# ERN_MainPower_2.net
KiCad netlist of a schematic drawn in Altium Designer
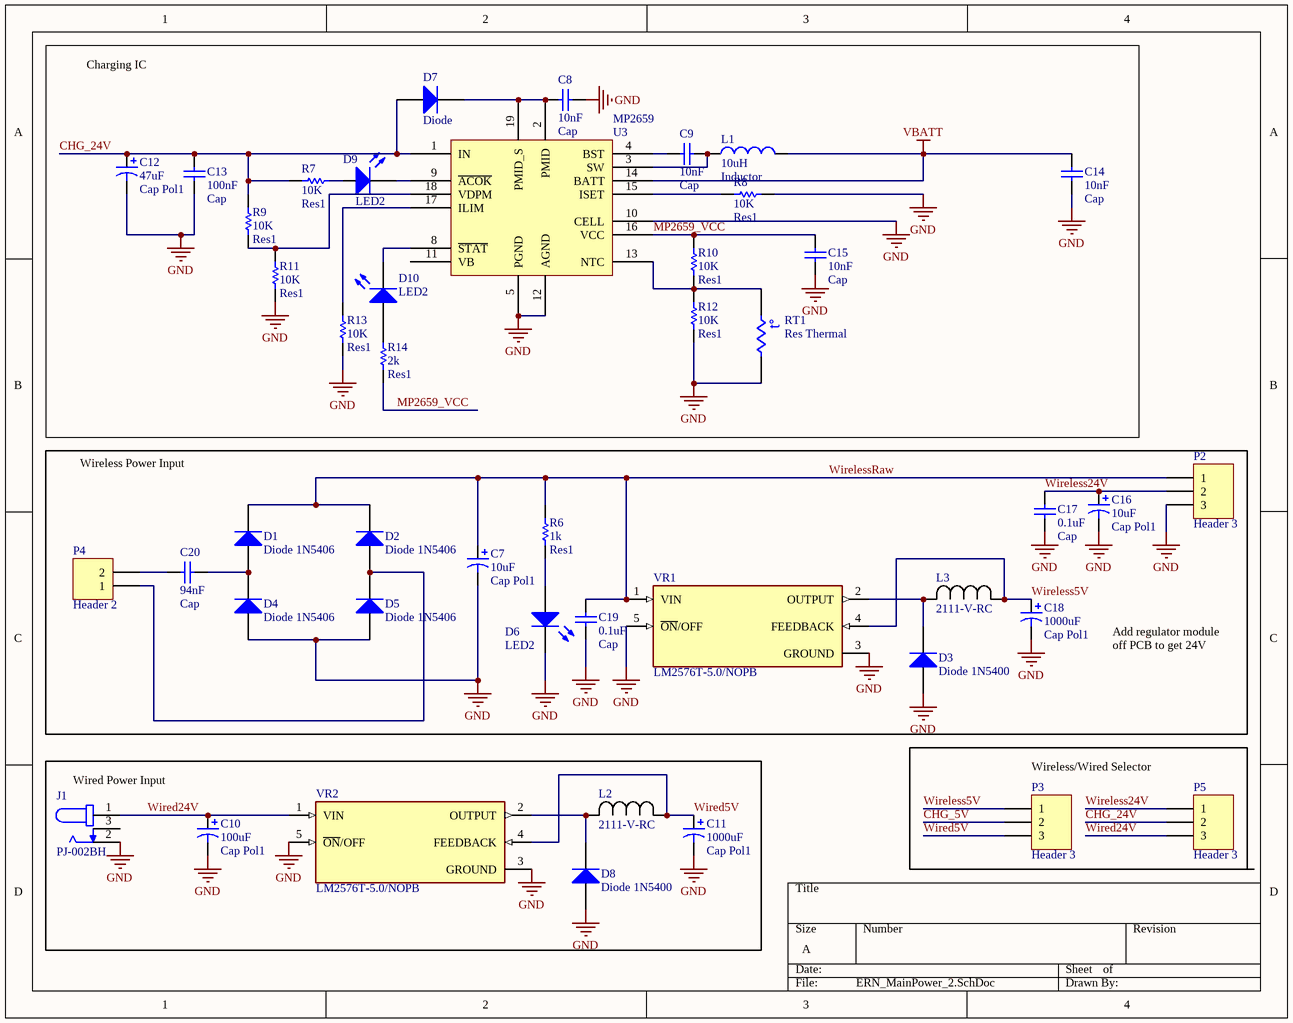
[diagram p0: ERN_MainPower_2.SchDoc]

(export (version "E")
  (design (tool "Eeschema 10.0.6"))
  (components
    (comp (ref "C7")
      (value "Cap Pol1")
      (footprint "RB7.6-15")
      (description "Polarized Capacitor (Radial)")
      (fields (field (name "ALTIUM_VALUE") "10uF") (field (name "PUBLISHER") "Altium Limited"))
      (libsource (lib "Miscellaneous Devices") (part "Cap Pol1"))
    )
    (comp (ref "C8")
      (value "Cap")
      (footprint "C0805")
      (description "Capacitor")
      (fields (field (name "ALTIUM_VALUE") "10nF") (field (name "PUBLISHER") "Altium Limited"))
      (libsource (lib "Miscellaneous Devices") (part "Cap"))
    )
    (comp (ref "C9")
      (value "Cap")
      (footprint "C0805")
      (description "Capacitor")
      (fields (field (name "ALTIUM_VALUE") "10nF") (field (name "PUBLISHER") "Altium Limited"))
      (libsource (lib "Miscellaneous Devices") (part "Cap"))
    )
    (comp (ref "C10")
      (value "Cap Pol1")
      (footprint "RB7.6-15")
      (description "Polarized Capacitor (Radial)")
      (fields (field (name "ALTIUM_VALUE") "100uF") (field (name "PUBLISHER") "Altium Limited"))
      (libsource (lib "Miscellaneous Devices") (part "Cap Pol1"))
    )
    (comp (ref "C11")
      (value "Cap Pol1")
      (footprint "RB7.6-15")
      (description "Polarized Capacitor (Radial)")
      (fields (field (name "ALTIUM_VALUE") "1000uF") (field (name "PUBLISHER") "Altium Limited"))
      (libsource (lib "Miscellaneous Devices") (part "Cap Pol1"))
    )
    (comp (ref "C12")
      (value "Cap Pol1")
      (footprint "RB7.6-15")
      (description "Polarized Capacitor (Radial)")
      (fields (field (name "ALTIUM_VALUE") "47uF") (field (name "PUBLISHER") "Altium Limited"))
      (libsource (lib "Miscellaneous Devices") (part "Cap Pol1"))
    )
    (comp (ref "C13")
      (value "Cap")
      (footprint "RAD-0.3")
      (description "Capacitor")
      (fields (field (name "ALTIUM_VALUE") "100nF") (field (name "PUBLISHER") "Altium Limited"))
      (libsource (lib "Miscellaneous Devices") (part "Cap"))
    )
    (comp (ref "C14")
      (value "Cap")
      (footprint "C0805")
      (description "Capacitor")
      (fields (field (name "ALTIUM_VALUE") "10nF") (field (name "PUBLISHER") "Altium Limited"))
      (libsource (lib "Miscellaneous Devices") (part "Cap"))
    )
    (comp (ref "C15")
      (value "Cap")
      (footprint "C0805")
      (description "Capacitor")
      (fields (field (name "ALTIUM_VALUE") "10nF") (field (name "PUBLISHER") "Altium Limited"))
      (libsource (lib "Miscellaneous Devices") (part "Cap"))
    )
    (comp (ref "C16")
      (value "Cap Pol1")
      (footprint "RB7.6-15")
      (description "Polarized Capacitor (Radial)")
      (fields (field (name "ALTIUM_VALUE") "10uF") (field (name "PUBLISHER") "Altium Limited"))
      (libsource (lib "Miscellaneous Devices") (part "Cap Pol1"))
    )
    (comp (ref "C17")
      (value "Cap")
      (footprint "RAD-0.3")
      (description "Capacitor")
      (fields (field (name "ALTIUM_VALUE") "0.1uF") (field (name "PUBLISHER") "Altium Limited"))
      (libsource (lib "Miscellaneous Devices") (part "Cap"))
    )
    (comp (ref "C18")
      (value "Cap Pol1")
      (footprint "RB7.6-15")
      (description "Polarized Capacitor (Radial)")
      (fields (field (name "ALTIUM_VALUE") "1000uF") (field (name "PUBLISHER") "Altium Limited"))
      (libsource (lib "Miscellaneous Devices") (part "Cap Pol1"))
    )
    (comp (ref "C19")
      (value "Cap")
      (footprint "RAD-0.3")
      (description "Capacitor")
      (fields (field (name "ALTIUM_VALUE") "0.1uF") (field (name "PUBLISHER") "Altium Limited"))
      (libsource (lib "Miscellaneous Devices") (part "Cap"))
    )
    (comp (ref "C20")
      (value "Cap")
      (footprint "C1210")
      (description "Capacitor")
      (fields (field (name "ALTIUM_VALUE") "94nF") (field (name "PUBLISHER") "Altium Limited"))
      (libsource (lib "Miscellaneous Devices") (part "Cap"))
    )
    (comp (ref "D1")
      (value "Diode 1N5406")
      (footprint "DO-201AD")
      (description "3 Amp General Purpose Rectifier")
      (fields (field (name "PUBLISHER") "Altium Limited"))
      (libsource (lib "Miscellaneous Devices") (part "Diode 1N5406"))
    )
    (comp (ref "D2")
      (value "Diode 1N5406")
      (footprint "DO-201AD")
      (description "3 Amp General Purpose Rectifier")
      (fields (field (name "PUBLISHER") "Altium Limited"))
      (libsource (lib "Miscellaneous Devices") (part "Diode 1N5406"))
    )
    (comp (ref "D3")
      (value "Diode 1N5400")
      (footprint "DO-201AD")
      (description "3 Amp General Purpose Rectifier")
      (fields (field (name "PUBLISHER") "Altium Limited"))
      (libsource (lib "Miscellaneous Devices") (part "Diode 1N5400"))
    )
    (comp (ref "D4")
      (value "Diode 1N5406")
      (footprint "DO-201AD")
      (description "3 Amp General Purpose Rectifier")
      (fields (field (name "PUBLISHER") "Altium Limited"))
      (libsource (lib "Miscellaneous Devices") (part "Diode 1N5406"))
    )
    (comp (ref "D5")
      (value "Diode 1N5406")
      (footprint "DO-201AD")
      (description "3 Amp General Purpose Rectifier")
      (fields (field (name "PUBLISHER") "Altium Limited"))
      (libsource (lib "Miscellaneous Devices") (part "Diode 1N5406"))
    )
    (comp (ref "D6")
      (value "LED2")
      (footprint "3.2X1.6X1.1")
      (description "Typical RED, GREEN, YELLOW, AMBER GaAs LED")
      (fields (field (name "PUBLISHER") "Altium Limited"))
      (libsource (lib "Miscellaneous Devices") (part "LED2"))
    )
    (comp (ref "D7")
      (value "Diode")
      (footprint "DIODE_SMC")
      (description "Default Diode")
      (fields (field (name "PUBLISHER") "Altium Limited"))
      (libsource (lib "Miscellaneous Devices") (part "Diode"))
    )
    (comp (ref "D8")
      (value "Diode 1N5400")
      (footprint "DO-201AD")
      (description "3 Amp General Purpose Rectifier")
      (fields (field (name "PUBLISHER") "Altium Limited"))
      (libsource (lib "Miscellaneous Devices") (part "Diode 1N5400"))
    )
    (comp (ref "D9")
      (value "LED2")
      (footprint "LED-0")
      (description "Typical RED, GREEN, YELLOW, AMBER GaAs LED")
      (fields (field (name "PUBLISHER") "Altium Limited"))
      (libsource (lib "Miscellaneous Devices") (part "LED2"))
    )
    (comp (ref "D10")
      (value "LED2")
      (footprint "LED-0")
      (description "Typical RED, GREEN, YELLOW, AMBER GaAs LED")
      (fields (field (name "PUBLISHER") "Altium Limited"))
      (libsource (lib "Miscellaneous Devices") (part "LED2"))
    )
    (comp (ref "J1")
      (value "PJ-002BH")
      (footprint "CUI_PJ-002BH")
      (description "2.5 x 6.5 mm, 5.0 A, Horizontal, Through Hole, Dc Power Jack Connector")
      (fields (field (name "MF") "Same Sky"))
      (libsource (lib "ERN") (part "PJ-002BH"))
    )
    (comp (ref "L1")
      (value "Inductor")
      (footprint "0402-A")
      (fields (field (name "ALTIUM_VALUE") "10uH") (field (name "PUBLISHER") "Altium Limited"))
      (libsource (lib "Miscellaneous Devices") (part "Inductor"))
    )
    (comp (ref "L2")
      (value "2111-V-RC")
      (footprint "IND_21XX_27A_V")
      (description "Inductor 68uH")
      (fields (field (name "COPYRIGHT") "Copyright (C) 2026 Ultra Librarian. All rights reserved."))
      (libsource (lib "ERN") (part "2111-V-RC"))
    )
    (comp (ref "L3")
      (value "2111-V-RC")
      (footprint "IND_21XX_27A_V")
      (description "Inductor 68uH")
      (fields (field (name "COPYRIGHT") "Copyright (C) 2026 Ultra Librarian. All rights reserved."))
      (libsource (lib "ERN") (part "2111-V-RC"))
    )
    (comp (ref "P2")
      (value "Header 3")
      (footprint "HDR1X3")
      (description "Header, 3-Pin")
      (fields (field (name "PUBLISHER") "Altium Limited"))
      (libsource (lib "Miscellaneous Connectors") (part "Header 3"))
    )
    (comp (ref "P3")
      (value "Header 3")
      (footprint "HDR1X3")
      (description "Header, 3-Pin")
      (fields (field (name "PUBLISHER") "Altium Limited"))
      (libsource (lib "Miscellaneous Connectors") (part "Header 3"))
    )
    (comp (ref "P4")
      (value "Header 2")
      (footprint "HDR1X2")
      (description "Header, 2-Pin")
      (fields (field (name "PUBLISHER") "Altium Limited"))
      (libsource (lib "Miscellaneous Connectors") (part "Header 2"))
    )
    (comp (ref "P5")
      (value "Header 3")
      (footprint "HDR1X3")
      (description "Header, 3-Pin")
      (fields (field (name "PUBLISHER") "Altium Limited"))
      (libsource (lib "Miscellaneous Connectors") (part "Header 3"))
    )
    (comp (ref "R6")
      (value "Res1")
      (footprint "AXIAL-0.3")
      (description "Resistor")
      (fields (field (name "ALTIUM_VALUE") "1k") (field (name "PUBLISHER") "Altium Limited"))
      (libsource (lib "Miscellaneous Devices") (part "Res1"))
    )
    (comp (ref "R7")
      (value "Res1")
      (footprint "AXIAL-0.3")
      (description "Resistor")
      (fields (field (name "ALTIUM_VALUE") "10K") (field (name "PUBLISHER") "Altium Limited"))
      (libsource (lib "Miscellaneous Devices") (part "Res1"))
    )
    (comp (ref "R8")
      (value "Res1")
      (footprint "AXIAL-0.3")
      (description "Resistor")
      (fields (field (name "ALTIUM_VALUE") "10K") (field (name "PUBLISHER") "Altium Limited"))
      (libsource (lib "Miscellaneous Devices") (part "Res1"))
    )
    (comp (ref "R9")
      (value "Res1")
      (footprint "AXIAL-0.3")
      (description "Resistor")
      (fields (field (name "ALTIUM_VALUE") "10K") (field (name "PUBLISHER") "Altium Limited"))
      (libsource (lib "Miscellaneous Devices") (part "Res1"))
    )
    (comp (ref "R10")
      (value "Res1")
      (footprint "AXIAL-0.3")
      (description "Resistor")
      (fields (field (name "ALTIUM_VALUE") "10K") (field (name "PUBLISHER") "Altium Limited"))
      (libsource (lib "Miscellaneous Devices") (part "Res1"))
    )
    (comp (ref "R11")
      (value "Res1")
      (footprint "AXIAL-0.3")
      (description "Resistor")
      (fields (field (name "ALTIUM_VALUE") "10K") (field (name "PUBLISHER") "Altium Limited"))
      (libsource (lib "Miscellaneous Devices") (part "Res1"))
    )
    (comp (ref "R12")
      (value "Res1")
      (footprint "AXIAL-0.3")
      (description "Resistor")
      (fields (field (name "ALTIUM_VALUE") "10K") (field (name "PUBLISHER") "Altium Limited"))
      (libsource (lib "Miscellaneous Devices") (part "Res1"))
    )
    (comp (ref "R13")
      (value "Res1")
      (footprint "AXIAL-0.3")
      (description "Resistor")
      (fields (field (name "ALTIUM_VALUE") "10K") (field (name "PUBLISHER") "Altium Limited"))
      (libsource (lib "Miscellaneous Devices") (part "Res1"))
    )
    (comp (ref "R14")
      (value "Res1")
      (footprint "AXIAL-0.3")
      (description "Resistor")
      (fields (field (name "ALTIUM_VALUE") "2k") (field (name "PUBLISHER") "Altium Limited"))
      (libsource (lib "Miscellaneous Devices") (part "Res1"))
    )
    (comp (ref "RT1")
      (value "Res Thermal")
      (footprint "AXIAL-0.3")
      (description "Thermistor")
      (fields (field (name "PUBLISHER") "Altium Limited"))
      (libsource (lib "Miscellaneous Devices") (part "Res Thermal"))
    )
    (comp (ref "U3")
      (value "MP2659")
      (footprint "MP2659_QFN19")
      (description "3S-6S Standalone Switching Charger")
      (libsource (lib "ERN") (part "MP2659"))
    )
    (comp (ref "VR1")
      (value "LM2576T-5.0/NOPB")
      (footprint "TO170P1067X483X1651-5")
      (description "SIMPLE SWITCHERÂ® 40V, 3A Low Component Count Step-Down Regulator")
      (fields (field (name "MF") "Texas Instruments"))
      (libsource (lib "ERN") (part "LM2576T-5.0/NOPB"))
    )
    (comp (ref "VR2")
      (value "LM2576T-5.0/NOPB")
      (footprint "TO170P1067X483X1651-5")
      (description "SIMPLE SWITCHERÂ® 40V, 3A Low Component Count Step-Down Regulator")
      (fields (field (name "MF") "Texas Instruments"))
      (libsource (lib "ERN") (part "LM2576T-5.0/NOPB"))
    )
  )
  (nets
    (net (code "1") (name "/CHG_5V") (class "Default")
      (node (ref "P3") (pin "2") (pinfunction "2_2") (pintype "passive"))
    )
    (net (code "2") (name "/CHG_24V") (class "Default")
      (node (ref "C12") (pin "1") (pinfunction "1_1") (pintype "passive"))
      (node (ref "C13") (pin "2") (pinfunction "2_2") (pintype "passive"))
      (node (ref "D7") (pin "1") (pinfunction "A_1") (pintype "passive"))
      (node (ref "P5") (pin "2") (pinfunction "2_2") (pintype "passive"))
      (node (ref "R7") (pin "2") (pinfunction "2_2") (pintype "passive"))
      (node (ref "R9") (pin "1") (pinfunction "1_1") (pintype "passive"))
      (node (ref "U3") (pin "1") (pinfunction "IN_1") (pintype "passive"))
    )
    (net (code "3") (name "/MP2659_VCC") (class "Default")
      (node (ref "C15") (pin "1") (pinfunction "1_1") (pintype "passive"))
      (node (ref "R10") (pin "2") (pinfunction "2_2") (pintype "passive"))
      (node (ref "R14") (pin "2") (pinfunction "2_2") (pintype "passive"))
      (node (ref "U3") (pin "16") (pinfunction "VCC_16") (pintype "passive"))
    )
    (net (code "4") (name "/Wired5V") (class "Default")
      (node (ref "C11") (pin "1") (pinfunction "1_1") (pintype "passive"))
      (node (ref "L2") (pin "1") (pinfunction "1_1") (pintype "passive"))
      (node (ref "P3") (pin "3") (pinfunction "3_3") (pintype "passive"))
      (node (ref "VR2") (pin "4") (pinfunction "FEEDBACK_4") (pintype "input"))
    )
    (net (code "5") (name "/Wired24V") (class "Default")
      (node (ref "C10") (pin "1") (pinfunction "1_1") (pintype "passive"))
      (node (ref "J1") (pin "1") (pinfunction "1_1") (pintype "passive"))
      (node (ref "P5") (pin "3") (pinfunction "3_3") (pintype "passive"))
      (node (ref "VR2") (pin "1") (pinfunction "VIN_1") (pintype "input"))
    )
    (net (code "6") (name "/Wireless5V") (class "Default")
      (node (ref "C18") (pin "1") (pinfunction "1_1") (pintype "passive"))
      (node (ref "L3") (pin "1") (pinfunction "1_1") (pintype "passive"))
      (node (ref "P3") (pin "1") (pinfunction "1_1") (pintype "passive"))
      (node (ref "VR1") (pin "4") (pinfunction "FEEDBACK_4") (pintype "input"))
    )
    (net (code "7") (name "/Wireless24V") (class "Default")
      (node (ref "C16") (pin "1") (pinfunction "1_1") (pintype "passive"))
      (node (ref "C17") (pin "1") (pinfunction "1_1") (pintype "passive"))
      (node (ref "P2") (pin "2") (pinfunction "2_2") (pintype "passive"))
      (node (ref "P5") (pin "1") (pinfunction "1_1") (pintype "passive"))
    )
    (net (code "8") (name "/WirelessRaw") (class "Default")
      (node (ref "C19") (pin "1") (pinfunction "1_1") (pintype "passive"))
      (node (ref "C7") (pin "1") (pinfunction "1_1") (pintype "passive"))
      (node (ref "D1") (pin "2") (pinfunction "K_2") (pintype "passive"))
      (node (ref "D2") (pin "2") (pinfunction "K_2") (pintype "passive"))
      (node (ref "P2") (pin "1") (pinfunction "1_1") (pintype "passive"))
      (node (ref "R6") (pin "2") (pinfunction "2_2") (pintype "passive"))
      (node (ref "VR1") (pin "1") (pinfunction "VIN_1") (pintype "input"))
    )
    (net (code "9") (name "GND") (class "Default")
      (node (ref "C10") (pin "2") (pinfunction "2_2") (pintype "passive"))
      (node (ref "C11") (pin "2") (pinfunction "2_2") (pintype "passive"))
      (node (ref "C12") (pin "2") (pinfunction "2_2") (pintype "passive"))
      (node (ref "C13") (pin "1") (pinfunction "1_1") (pintype "passive"))
      (node (ref "C14") (pin "2") (pinfunction "2_2") (pintype "passive"))
      (node (ref "C15") (pin "2") (pinfunction "2_2") (pintype "passive"))
      (node (ref "C16") (pin "2") (pinfunction "2_2") (pintype "passive"))
      (node (ref "C17") (pin "2") (pinfunction "2_2") (pintype "passive"))
      (node (ref "C18") (pin "2") (pinfunction "2_2") (pintype "passive"))
      (node (ref "C19") (pin "2") (pinfunction "2_2") (pintype "passive"))
      (node (ref "C7") (pin "2") (pinfunction "2_2") (pintype "passive"))
      (node (ref "C8") (pin "1") (pinfunction "1_1") (pintype "passive"))
      (node (ref "D3") (pin "1") (pinfunction "A_1") (pintype "passive"))
      (node (ref "D4") (pin "1") (pinfunction "A_1") (pintype "passive"))
      (node (ref "D5") (pin "1") (pinfunction "A_1") (pintype "passive"))
      (node (ref "D6") (pin "2") (pinfunction "K_2") (pintype "passive"))
      (node (ref "D8") (pin "1") (pinfunction "A_1") (pintype "passive"))
      (node (ref "J1") (pin "2") (pinfunction "2_2") (pintype "passive"))
      (node (ref "P2") (pin "3") (pinfunction "3_3") (pintype "passive"))
      (node (ref "R11") (pin "2") (pinfunction "2_2") (pintype "passive"))
      (node (ref "R12") (pin "1") (pinfunction "1_1") (pintype "passive"))
      (node (ref "R13") (pin "2") (pinfunction "2_2") (pintype "passive"))
      (node (ref "R8") (pin "2") (pinfunction "2_2") (pintype "passive"))
      (node (ref "RT1") (pin "2") (pinfunction "2_2") (pintype "passive"))
      (node (ref "U3") (pin "10") (pinfunction "CELL_10") (pintype "passive"))
      (node (ref "U3") (pin "12") (pinfunction "AGND_12") (pintype "passive"))
      (node (ref "U3") (pin "5") (pinfunction "PGND_5") (pintype "passive"))
      (node (ref "VR1") (pin "3") (pinfunction "GROUND_3") (pintype "power_in"))
      (node (ref "VR1") (pin "5") (pinfunction "~{ON}/OFF_5") (pintype "input"))
      (node (ref "VR2") (pin "3") (pinfunction "GROUND_3") (pintype "power_in"))
      (node (ref "VR2") (pin "5") (pinfunction "~{ON}/OFF_5") (pintype "input"))
    )
    (net (code "10") (name "Net-(C20-Pad1)") (class "Default")
      (node (ref "C20") (pin "1") (pinfunction "1_1") (pintype "passive"))
      (node (ref "P4") (pin "2") (pinfunction "2_2") (pintype "passive"))
    )
    (net (code "11") (name "Net-(D1-A)") (class "Default")
      (node (ref "C20") (pin "2") (pinfunction "2_2") (pintype "passive"))
      (node (ref "D1") (pin "1") (pinfunction "A_1") (pintype "passive"))
      (node (ref "D4") (pin "2") (pinfunction "K_2") (pintype "passive"))
    )
    (net (code "12") (name "Net-(D2-A)") (class "Default")
      (node (ref "D2") (pin "1") (pinfunction "A_1") (pintype "passive"))
      (node (ref "D5") (pin "2") (pinfunction "K_2") (pintype "passive"))
      (node (ref "P4") (pin "1") (pinfunction "1_1") (pintype "passive"))
    )
    (net (code "13") (name "Net-(D3-K)") (class "Default")
      (node (ref "D3") (pin "2") (pinfunction "K_2") (pintype "passive"))
      (node (ref "L3") (pin "2") (pinfunction "2_2") (pintype "passive"))
      (node (ref "VR1") (pin "2") (pinfunction "OUTPUT_2") (pintype "output"))
    )
    (net (code "14") (name "Net-(D6-A)") (class "Default")
      (node (ref "D6") (pin "1") (pinfunction "A_1") (pintype "passive"))
      (node (ref "R6") (pin "1") (pinfunction "1_1") (pintype "passive"))
    )
    (net (code "15") (name "Net-(D7-K)") (class "Default")
      (node (ref "C8") (pin "2") (pinfunction "2_2") (pintype "passive"))
      (node (ref "D7") (pin "2") (pinfunction "K_2") (pintype "passive"))
      (node (ref "U3") (pin "19") (pinfunction "PMID_S_19") (pintype "passive"))
      (node (ref "U3") (pin "2") (pinfunction "PMID_2") (pintype "passive"))
    )
    (net (code "16") (name "Net-(D8-K)") (class "Default")
      (node (ref "D8") (pin "2") (pinfunction "K_2") (pintype "passive"))
      (node (ref "L2") (pin "2") (pinfunction "2_2") (pintype "passive"))
      (node (ref "VR2") (pin "2") (pinfunction "OUTPUT_2") (pintype "output"))
    )
    (net (code "17") (name "Net-(D9-A)") (class "Default")
      (node (ref "D9") (pin "1") (pinfunction "A_1") (pintype "passive"))
      (node (ref "R7") (pin "1") (pinfunction "1_1") (pintype "passive"))
    )
    (net (code "18") (name "Net-(D9-K)") (class "Default")
      (node (ref "D9") (pin "2") (pinfunction "K_2") (pintype "passive"))
      (node (ref "U3") (pin "9") (pinfunction "~{ACOK}_9") (pintype "passive"))
    )
    (net (code "19") (name "Net-(D10-A)") (class "Default")
      (node (ref "D10") (pin "1") (pinfunction "A_1") (pintype "passive"))
      (node (ref "R14") (pin "1") (pinfunction "1_1") (pintype "passive"))
    )
    (net (code "20") (name "Net-(D10-K)") (class "Default")
      (node (ref "D10") (pin "2") (pinfunction "K_2") (pintype "passive"))
      (node (ref "U3") (pin "8") (pinfunction "~{STAT}_8") (pintype "passive"))
    )
    (net (code "21") (name "Net-(U3-BST)") (class "Default")
      (node (ref "C9") (pin "2") (pinfunction "2_2") (pintype "passive"))
      (node (ref "U3") (pin "4") (pinfunction "BST_4") (pintype "passive"))
    )
    (net (code "22") (name "Net-(U3-ILIM)") (class "Default")
      (node (ref "R13") (pin "1") (pinfunction "1_1") (pintype "passive"))
      (node (ref "U3") (pin "17") (pinfunction "ILIM_17") (pintype "passive"))
    )
    (net (code "23") (name "Net-(U3-ISET)") (class "Default")
      (node (ref "R8") (pin "1") (pinfunction "1_1") (pintype "passive"))
      (node (ref "U3") (pin "15") (pinfunction "ISET_15") (pintype "passive"))
    )
    (net (code "24") (name "Net-(U3-NTC)") (class "Default")
      (node (ref "R10") (pin "1") (pinfunction "1_1") (pintype "passive"))
      (node (ref "R12") (pin "2") (pinfunction "2_2") (pintype "passive"))
      (node (ref "RT1") (pin "1") (pinfunction "1_1") (pintype "passive"))
      (node (ref "U3") (pin "13") (pinfunction "NTC_13") (pintype "passive"))
    )
    (net (code "25") (name "Net-(U3-SW)") (class "Default")
      (node (ref "C9") (pin "1") (pinfunction "1_1") (pintype "passive"))
      (node (ref "L1") (pin "1") (pinfunction "1_1") (pintype "passive"))
      (node (ref "U3") (pin "3") (pinfunction "SW_3") (pintype "passive"))
    )
    (net (code "26") (name "Net-(U3-VDPM)") (class "Default")
      (node (ref "R11") (pin "1") (pinfunction "1_1") (pintype "passive"))
      (node (ref "R9") (pin "2") (pinfunction "2_2") (pintype "passive"))
      (node (ref "U3") (pin "18") (pinfunction "VDPM_18") (pintype "passive"))
    )
    (net (code "27") (name "VBATT") (class "Default")
      (node (ref "C14") (pin "1") (pinfunction "1_1") (pintype "passive"))
      (node (ref "L1") (pin "2") (pinfunction "2_2") (pintype "passive"))
      (node (ref "U3") (pin "14") (pinfunction "BATT_14") (pintype "passive"))
    )
    (net (code "28") (name "unconnected-(J1-Pad3)") (class "Default")
      (node (ref "J1") (pin "3") (pinfunction "3_3") (pintype "passive"))
    )
    (net (code "29") (name "unconnected-(U3-VB-Pad11)") (class "Default")
      (node (ref "U3") (pin "11") (pinfunction "VB_11") (pintype "passive"))
    )
  )
)
